# LIC_rack_CV-01.net
KiCad netlist of a schematic drawn in EAGLE
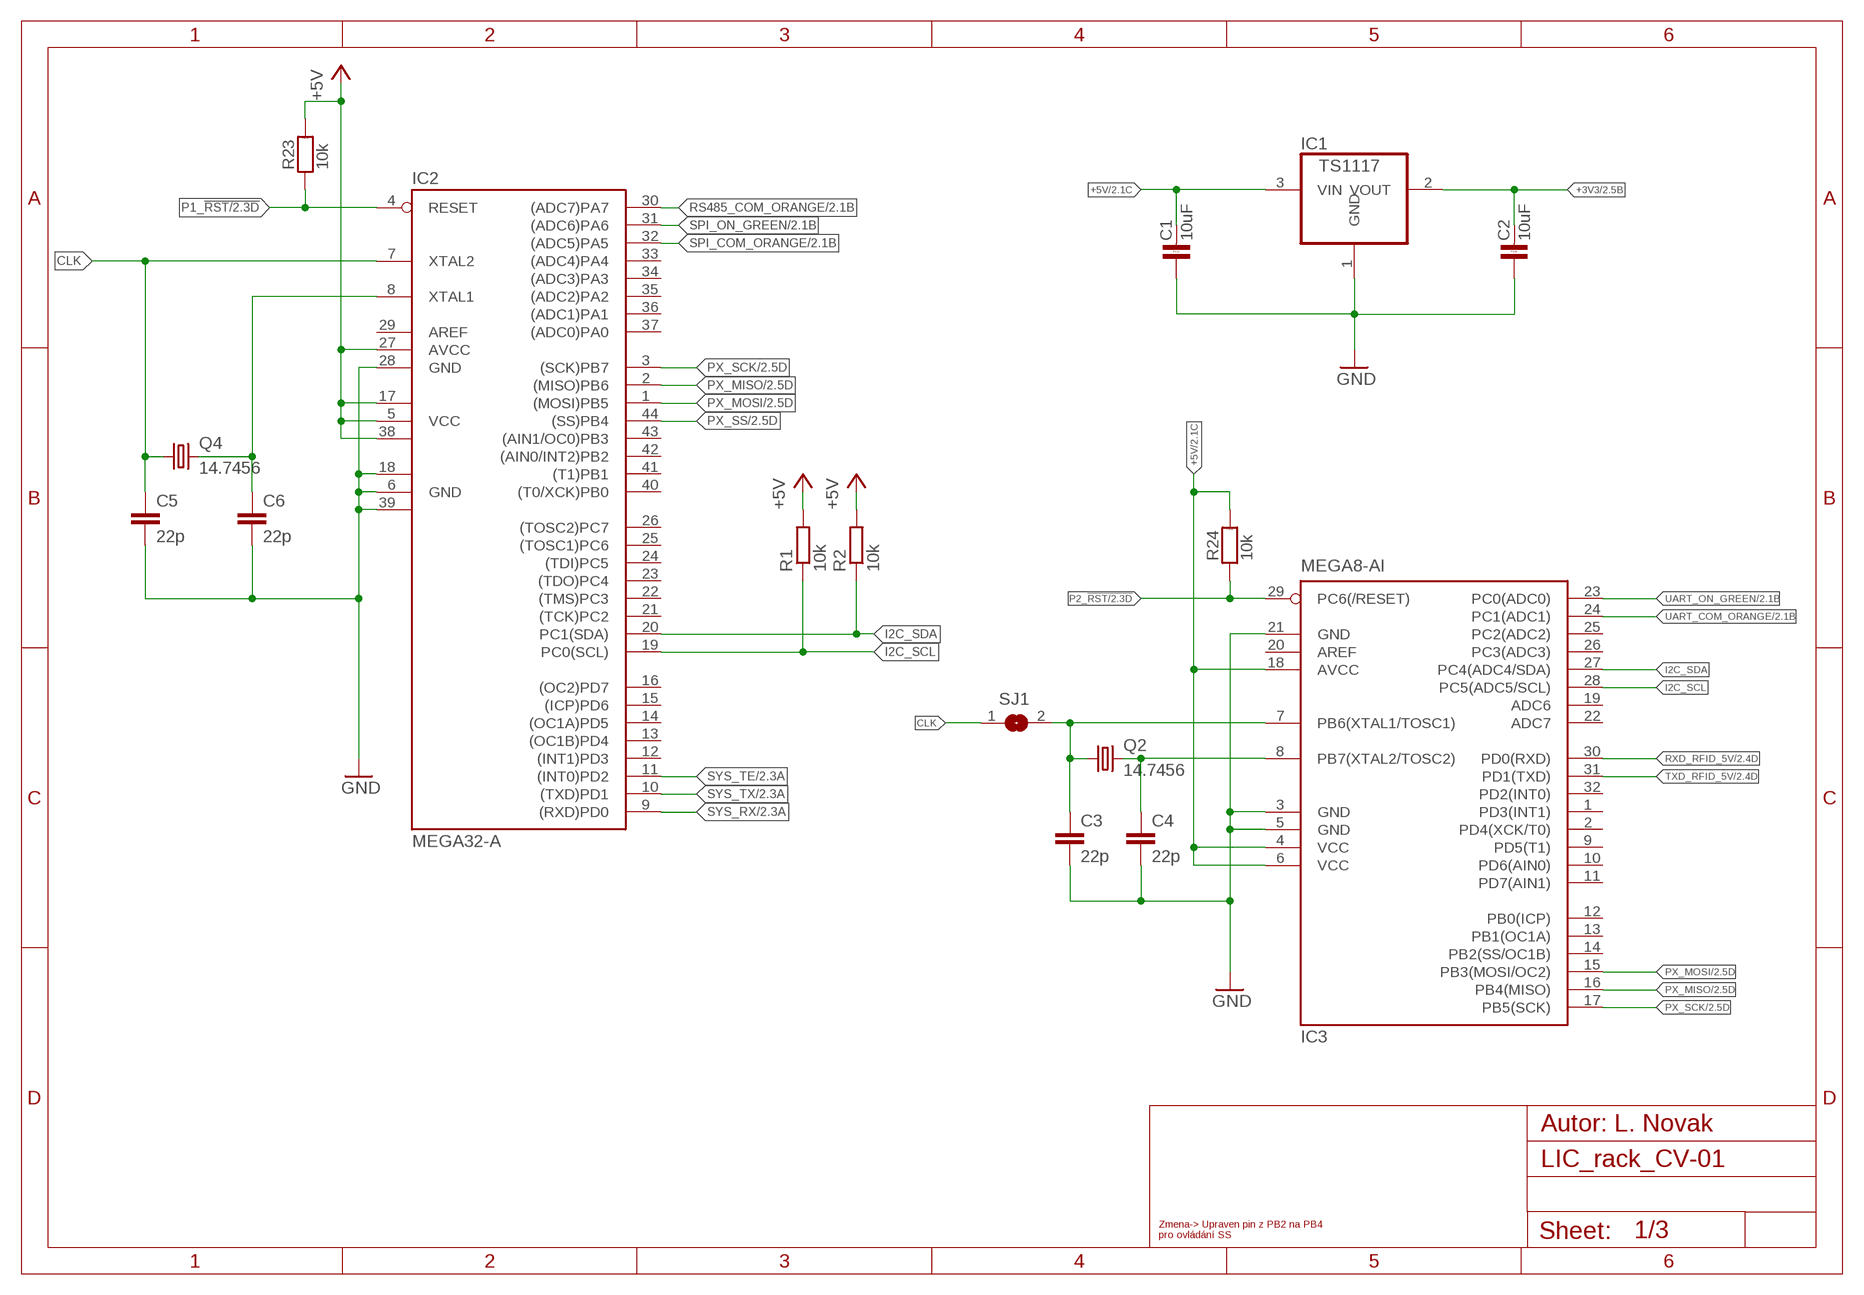
[diagram p0: schematic, sheet 1]
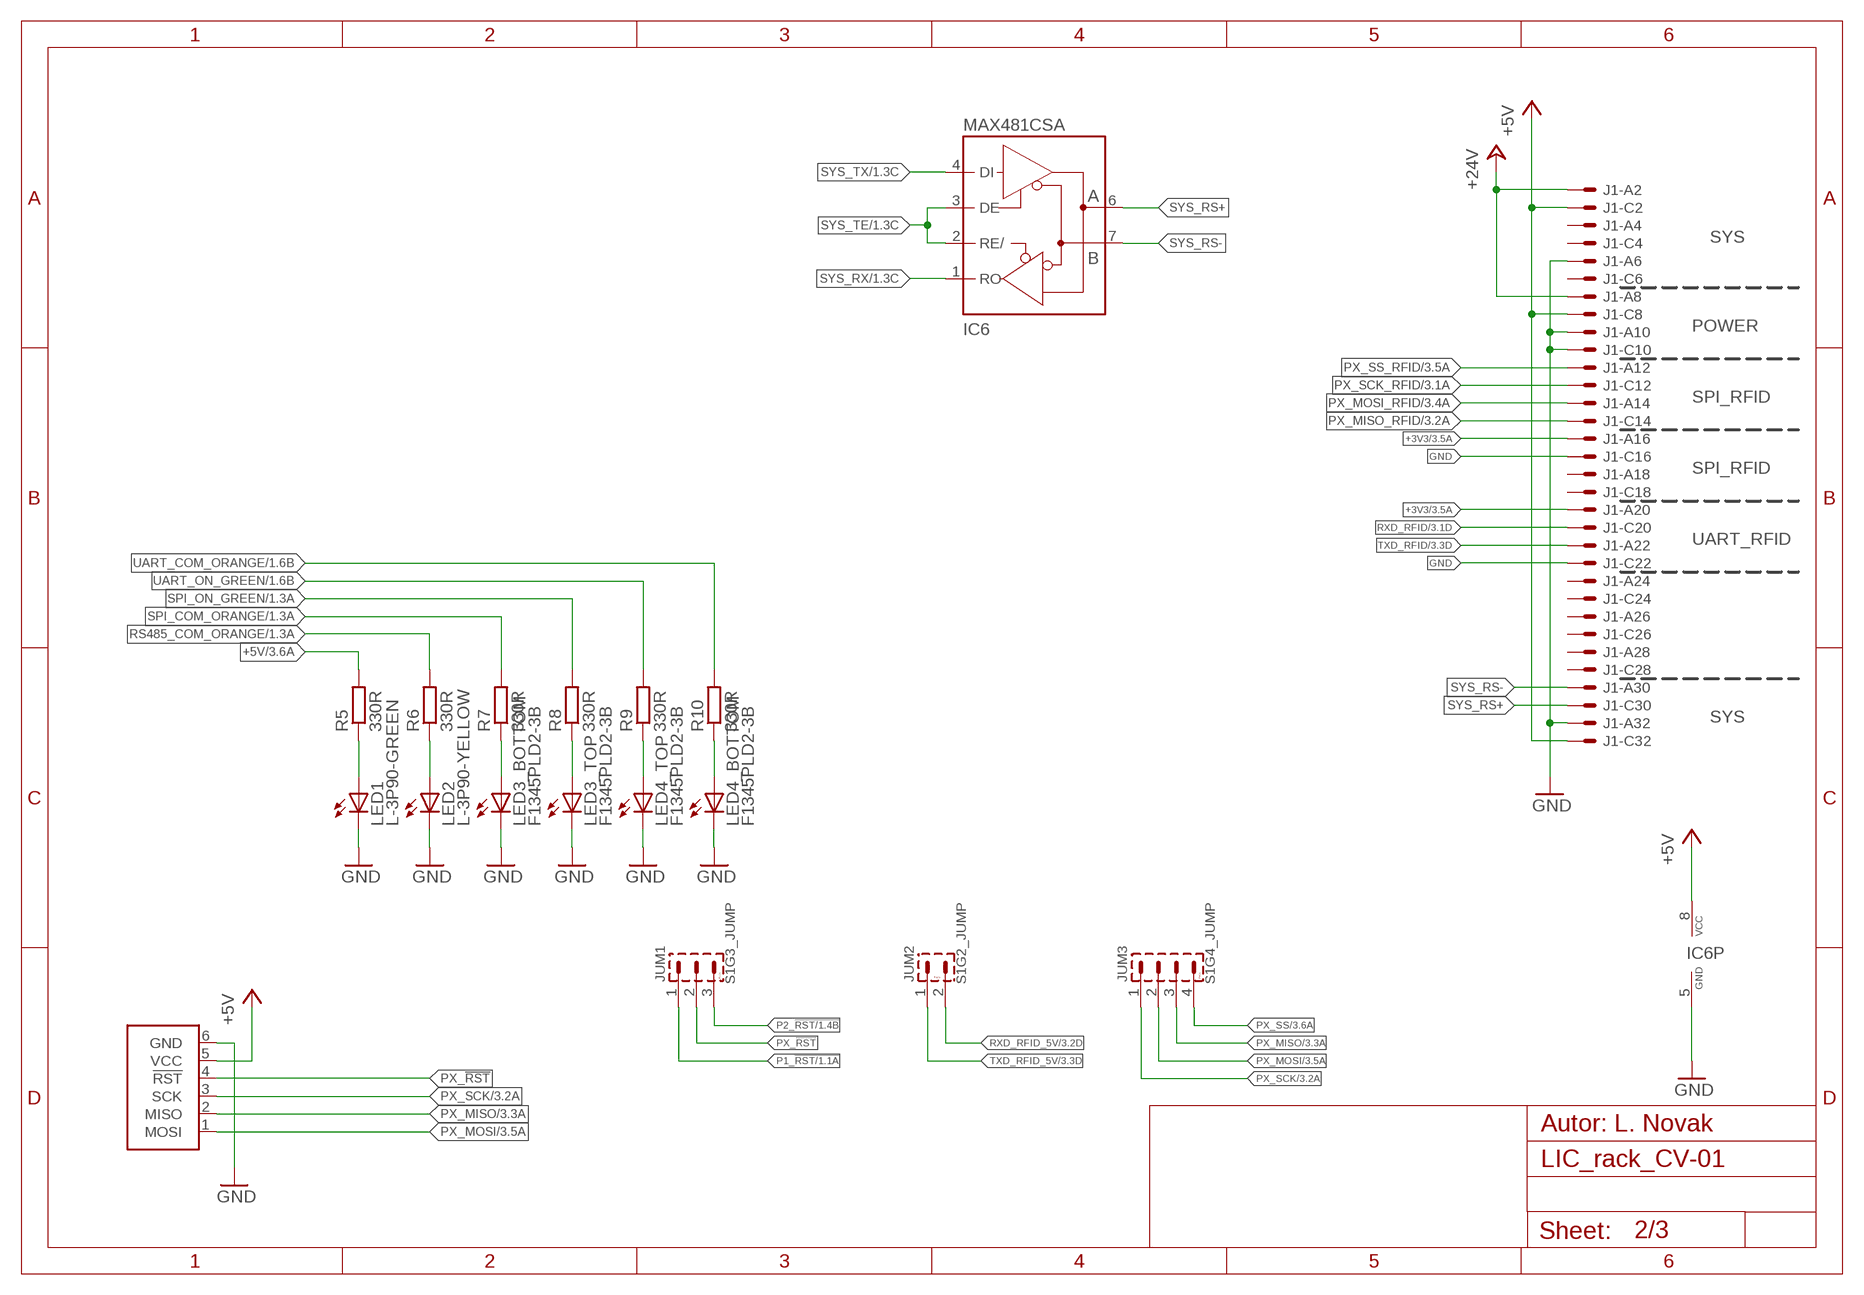
[diagram p1: schematic, sheet 2]
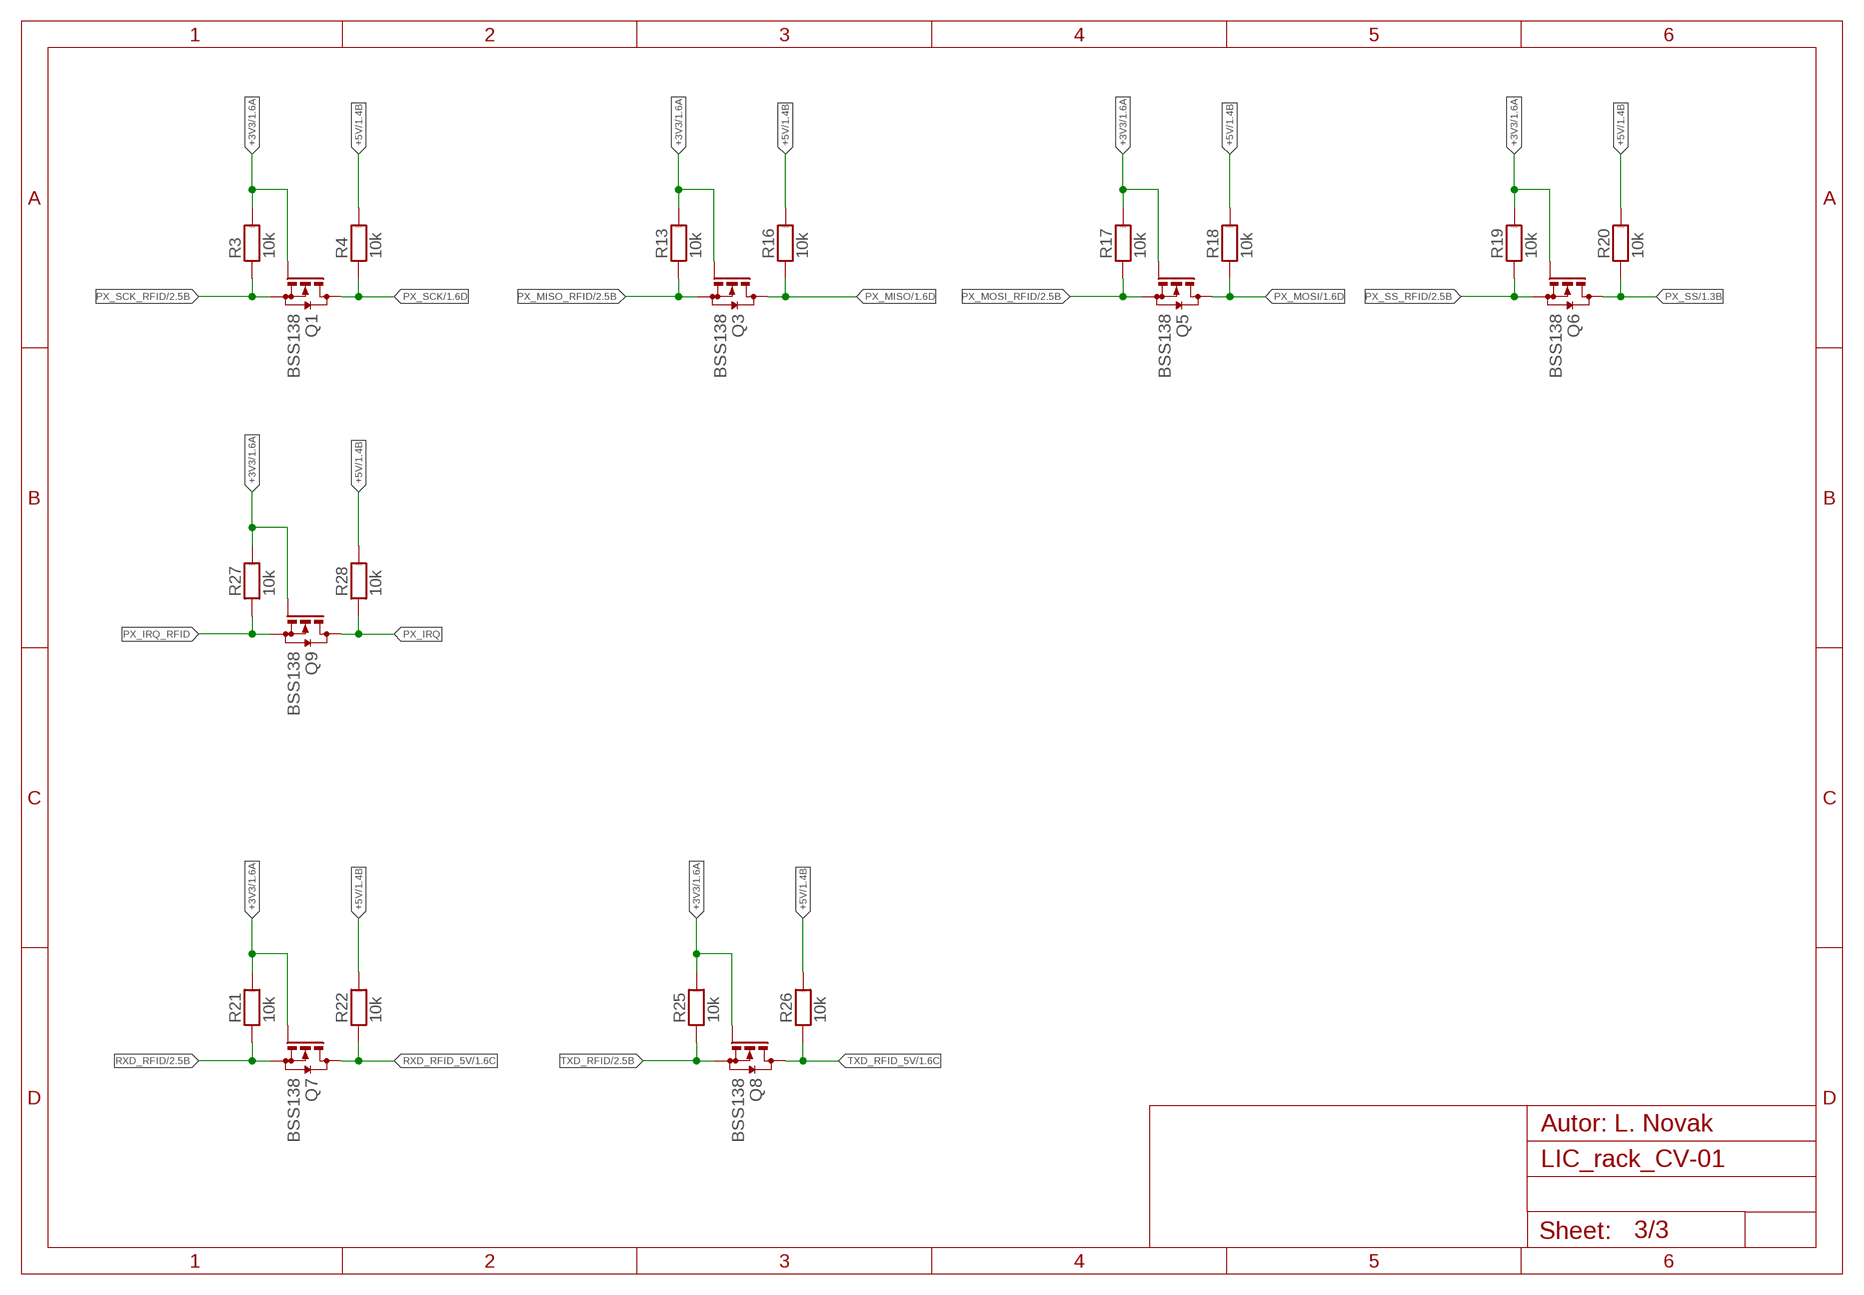
[diagram p2: schematic, sheet 3]

(export (version "E")
  (design (tool "Eeschema 10.0.6"))
  (components
    (comp (ref "C1")
      (value "10uF")
      (footprint "eagle-import:1206")
      (libsource (lib "eagle-import") (part "C-KER_1206"))
    )
    (comp (ref "C2")
      (value "10uF")
      (footprint "eagle-import:1206")
      (libsource (lib "eagle-import") (part "C-KER_1206"))
    )
    (comp (ref "C3")
      (value "22p")
      (footprint "eagle-import:C0805")
      (libsource (lib "eagle-import") (part "C-EUC0805"))
    )
    (comp (ref "C4")
      (value "22p")
      (footprint "eagle-import:C0805")
      (libsource (lib "eagle-import") (part "C-EUC0805"))
    )
    (comp (ref "C5")
      (value "22p")
      (footprint "eagle-import:C0805")
      (libsource (lib "eagle-import") (part "C-EUC0805"))
    )
    (comp (ref "C6")
      (value "22p")
      (footprint "eagle-import:C0805")
      (libsource (lib "eagle-import") (part "C-EUC0805"))
    )
    (comp (ref "IC1")
      (value "TS1117")
      (footprint "eagle-import:SOT223")
      (fields (field (name "MPN") "REG1117"))
      (libsource (lib "eagle-import") (part "REG1117"))
    )
    (comp (ref "IC2")
      (value "MEGA32-A")
      (footprint "eagle-import:TQFP44")
      (fields (field (name "MPN") "ATMEGA32-16AU"))
      (libsource (lib "eagle-import") (part "MEGA32-A"))
    )
    (comp (ref "IC3")
      (value "MEGA8-AI")
      (footprint "eagle-import:TQFP32-08")
      (fields (field (name "MPN") "ATMEGA8-16AU"))
      (libsource (lib "eagle-import") (part "MEGA8-AI"))
    )
    (comp (ref "Q2")
      (value "14.7456")
      (footprint "eagle-import:HC49U70")
      (libsource (lib "eagle-import") (part "XTAL"))
    )
    (comp (ref "Q4")
      (value "14.7456")
      (footprint "eagle-import:HC49U70")
      (libsource (lib "eagle-import") (part "XTAL"))
    )
    (comp (ref "R1")
      (value "10k")
      (footprint "eagle-import:R1206")
      (libsource (lib "eagle-import") (part "R-EU_R1206"))
    )
    (comp (ref "R2")
      (value "10k")
      (footprint "eagle-import:R1206")
      (libsource (lib "eagle-import") (part "R-EU_R1206"))
    )
    (comp (ref "R23")
      (value "10k")
      (footprint "eagle-import:1206")
      (libsource (lib "eagle-import") (part "R_1206"))
    )
    (comp (ref "R24")
      (value "10k")
      (footprint "eagle-import:1206")
      (libsource (lib "eagle-import") (part "R_1206"))
    )
    (comp (ref "SJ1") (value "SJ") (footprint "eagle-import:SJ") (libsource (lib "eagle-import") (part "SJ")))
    (comp (ref "IC6")
      (value "MAX481CSA")
      (footprint "eagle-import:SO08")
      (libsource (lib "eagle-import") (part "MAX481CSA"))
    )
    (comp (ref "J1")
      (value "VG32SP")
      (footprint "eagle-import:VG32P")
      (libsource (lib "eagle-import") (part "VG32SP"))
    )
    (comp (ref "JUM1")
      (value "S1G3_JUMP")
      (footprint "eagle-import:S1G3_JUM")
      (libsource (lib "eagle-import") (part "S1G3_JUMP"))
    )
    (comp (ref "JUM2")
      (value "S1G2_JUMP")
      (footprint "eagle-import:S1G2_JUM")
      (libsource (lib "eagle-import") (part "S1G2_JUMP"))
    )
    (comp (ref "JUM3")
      (value "S1G4_JUMP")
      (footprint "eagle-import:S1G4_JUM")
      (libsource (lib "eagle-import") (part "S1G4_JUMP"))
    )
    (comp (ref "LED1")
      (value "L-3P90-GREEN")
      (footprint "eagle-import:L-3P90")
      (libsource (lib "eagle-import") (part "L-3P90-GREEN"))
    )
    (comp (ref "LED2")
      (value "L-3P90-YELLOW")
      (footprint "eagle-import:L-3P90")
      (libsource (lib "eagle-import") (part "L-3P90-YELLOW"))
    )
    (comp (ref "LED3")
      (value "F1345PLD2-3B")
      (footprint "eagle-import:F1345PLD2-3B")
      (libsource (lib "eagle-import") (part "F1345PLD2-3B"))
    )
    (comp (ref "LED4")
      (value "F1345PLD2-3B")
      (footprint "eagle-import:F1345PLD2-3B")
      (libsource (lib "eagle-import") (part "F1345PLD2-3B"))
    )
    (comp (ref "R5")
      (value "330R")
      (footprint "eagle-import:R1206")
      (libsource (lib "eagle-import") (part "R-EU_R1206"))
    )
    (comp (ref "R6")
      (value "330R")
      (footprint "eagle-import:R1206")
      (libsource (lib "eagle-import") (part "R-EU_R1206"))
    )
    (comp (ref "R7")
      (value "330R")
      (footprint "eagle-import:R1206")
      (libsource (lib "eagle-import") (part "R-EU_R1206"))
    )
    (comp (ref "R8")
      (value "330R")
      (footprint "eagle-import:R1206")
      (libsource (lib "eagle-import") (part "R-EU_R1206"))
    )
    (comp (ref "R9")
      (value "330R")
      (footprint "eagle-import:R1206")
      (libsource (lib "eagle-import") (part "R-EU_R1206"))
    )
    (comp (ref "R10")
      (value "330R")
      (footprint "eagle-import:R1206")
      (libsource (lib "eagle-import") (part "R-EU_R1206"))
    )
    (comp (ref "U1")
      (value "ATPROG-V")
      (footprint "eagle-import:6410-06")
      (libsource (lib "eagle-import") (part "ATPROG-V"))
    )
    (comp (ref "Q1")
      (value "BSS138")
      (footprint "eagle-import:SOT23")
      (libsource (lib "eagle-import") (part "BSS123"))
    )
    (comp (ref "Q3")
      (value "BSS138")
      (footprint "eagle-import:SOT23")
      (libsource (lib "eagle-import") (part "BSS123"))
    )
    (comp (ref "Q5")
      (value "BSS138")
      (footprint "eagle-import:SOT23")
      (libsource (lib "eagle-import") (part "BSS123"))
    )
    (comp (ref "Q6")
      (value "BSS138")
      (footprint "eagle-import:SOT23")
      (libsource (lib "eagle-import") (part "BSS123"))
    )
    (comp (ref "Q7")
      (value "BSS138")
      (footprint "eagle-import:SOT23")
      (libsource (lib "eagle-import") (part "BSS123"))
    )
    (comp (ref "Q8")
      (value "BSS138")
      (footprint "eagle-import:SOT23")
      (libsource (lib "eagle-import") (part "BSS123"))
    )
    (comp (ref "Q9")
      (value "BSS138")
      (footprint "eagle-import:SOT23")
      (libsource (lib "eagle-import") (part "BSS123"))
    )
    (comp (ref "R3")
      (value "10k")
      (footprint "eagle-import:1206")
      (libsource (lib "eagle-import") (part "R_1206"))
    )
    (comp (ref "R4")
      (value "10k")
      (footprint "eagle-import:1206")
      (libsource (lib "eagle-import") (part "R_1206"))
    )
    (comp (ref "R13")
      (value "10k")
      (footprint "eagle-import:1206")
      (libsource (lib "eagle-import") (part "R_1206"))
    )
    (comp (ref "R16")
      (value "10k")
      (footprint "eagle-import:1206")
      (libsource (lib "eagle-import") (part "R_1206"))
    )
    (comp (ref "R17")
      (value "10k")
      (footprint "eagle-import:1206")
      (libsource (lib "eagle-import") (part "R_1206"))
    )
    (comp (ref "R18")
      (value "10k")
      (footprint "eagle-import:1206")
      (libsource (lib "eagle-import") (part "R_1206"))
    )
    (comp (ref "R19")
      (value "10k")
      (footprint "eagle-import:1206")
      (libsource (lib "eagle-import") (part "R_1206"))
    )
    (comp (ref "R20")
      (value "10k")
      (footprint "eagle-import:1206")
      (libsource (lib "eagle-import") (part "R_1206"))
    )
    (comp (ref "R21")
      (value "10k")
      (footprint "eagle-import:1206")
      (libsource (lib "eagle-import") (part "R_1206"))
    )
    (comp (ref "R22")
      (value "10k")
      (footprint "eagle-import:1206")
      (libsource (lib "eagle-import") (part "R_1206"))
    )
    (comp (ref "R25")
      (value "10k")
      (footprint "eagle-import:1206")
      (libsource (lib "eagle-import") (part "R_1206"))
    )
    (comp (ref "R26")
      (value "10k")
      (footprint "eagle-import:1206")
      (libsource (lib "eagle-import") (part "R_1206"))
    )
    (comp (ref "R27")
      (value "10k")
      (footprint "eagle-import:1206")
      (libsource (lib "eagle-import") (part "R_1206"))
    )
    (comp (ref "R28")
      (value "10k")
      (footprint "eagle-import:1206")
      (libsource (lib "eagle-import") (part "R_1206"))
    )
  )
  (nets
    (net (code "1") (name "+3V3") (class "Default")
      (node (ref "C2") (pin "2") (pinfunction "2_2") (pintype "passive"))
      (node (ref "IC1") (pin "2") (pinfunction "VOUT_2") (pintype "output"))
      (node (ref "J1") (pin "A16") (pinfunction "MS_A16") (pintype "passive"))
      (node (ref "J1") (pin "A20") (pinfunction "MS_A20") (pintype "passive"))
      (node (ref "Q1") (pin "1") (pinfunction "G_1") (pintype "passive"))
      (node (ref "Q3") (pin "1") (pinfunction "G_1") (pintype "passive"))
      (node (ref "Q5") (pin "1") (pinfunction "G_1") (pintype "passive"))
      (node (ref "Q6") (pin "1") (pinfunction "G_1") (pintype "passive"))
      (node (ref "Q7") (pin "1") (pinfunction "G_1") (pintype "passive"))
      (node (ref "Q8") (pin "1") (pinfunction "G_1") (pintype "passive"))
      (node (ref "Q9") (pin "1") (pinfunction "G_1") (pintype "passive"))
      (node (ref "R13") (pin "2") (pinfunction "2_2") (pintype "passive"))
      (node (ref "R17") (pin "2") (pinfunction "2_2") (pintype "passive"))
      (node (ref "R19") (pin "2") (pinfunction "2_2") (pintype "passive"))
      (node (ref "R21") (pin "2") (pinfunction "2_2") (pintype "passive"))
      (node (ref "R25") (pin "2") (pinfunction "2_2") (pintype "passive"))
      (node (ref "R27") (pin "2") (pinfunction "2_2") (pintype "passive"))
      (node (ref "R3") (pin "2") (pinfunction "2_2") (pintype "passive"))
    )
    (net (code "2") (name "+5V") (class "Default")
      (node (ref "C1") (pin "2") (pinfunction "2_2") (pintype "passive"))
      (node (ref "IC1") (pin "3") (pinfunction "VIN_3") (pintype "input"))
      (node (ref "IC2") (pin "17") (pinfunction "VCC1_17") (pintype "power_in"))
      (node (ref "IC2") (pin "27") (pinfunction "AVCC_27") (pintype "power_in"))
      (node (ref "IC2") (pin "38") (pinfunction "VCC2_38") (pintype "power_in"))
      (node (ref "IC2") (pin "5") (pinfunction "VCC_5") (pintype "power_in"))
      (node (ref "IC3") (pin "18") (pinfunction "AVCC_18") (pintype "power_in"))
      (node (ref "IC3") (pin "4") (pinfunction "VCC_4") (pintype "power_in"))
      (node (ref "IC3") (pin "6") (pinfunction "VCC_6") (pintype "power_in"))
      (node (ref "IC6") (pin "8") (pinfunction "VCC_8") (pintype "power_in"))
      (node (ref "J1") (pin "C2") (pinfunction "MS_C2") (pintype "passive"))
      (node (ref "J1") (pin "C32") (pinfunction "MSV_C32") (pintype "passive"))
      (node (ref "J1") (pin "C8") (pinfunction "MS_C8") (pintype "passive"))
      (node (ref "R1") (pin "2") (pinfunction "2_2") (pintype "passive"))
      (node (ref "R16") (pin "2") (pinfunction "2_2") (pintype "passive"))
      (node (ref "R18") (pin "2") (pinfunction "2_2") (pintype "passive"))
      (node (ref "R2") (pin "2") (pinfunction "2_2") (pintype "passive"))
      (node (ref "R20") (pin "2") (pinfunction "2_2") (pintype "passive"))
      (node (ref "R22") (pin "2") (pinfunction "2_2") (pintype "passive"))
      (node (ref "R23") (pin "2") (pinfunction "2_2") (pintype "passive"))
      (node (ref "R24") (pin "2") (pinfunction "2_2") (pintype "passive"))
      (node (ref "R26") (pin "2") (pinfunction "2_2") (pintype "passive"))
      (node (ref "R28") (pin "2") (pinfunction "2_2") (pintype "passive"))
      (node (ref "R4") (pin "2") (pinfunction "2_2") (pintype "passive"))
      (node (ref "R5") (pin "2") (pinfunction "2_2") (pintype "passive"))
      (node (ref "U1") (pin "5") (pinfunction "VCC_5") (pintype "power_in"))
    )
    (net (code "3") (name "+24V") (class "Default")
      (node (ref "J1") (pin "A2") (pinfunction "MS_A2") (pintype "passive"))
      (node (ref "J1") (pin "A8") (pinfunction "MS_A8") (pintype "passive"))
    )
    (net (code "4") (name "CLK") (class "Default")
      (node (ref "C5") (pin "1") (pinfunction "1_1") (pintype "passive"))
      (node (ref "IC2") (pin "7") (pinfunction "XTAL2_7") (pintype "bidirectional"))
      (node (ref "Q4") (pin "1") (pinfunction "1_1") (pintype "passive"))
      (node (ref "SJ1") (pin "1") (pinfunction "1_1") (pintype "passive"))
    )
    (net (code "5") (name "GND") (class "Default")
      (node (ref "C1") (pin "1") (pinfunction "1_1") (pintype "passive"))
      (node (ref "C2") (pin "1") (pinfunction "1_1") (pintype "passive"))
      (node (ref "C3") (pin "2") (pinfunction "2_2") (pintype "passive"))
      (node (ref "C4") (pin "2") (pinfunction "2_2") (pintype "passive"))
      (node (ref "C5") (pin "2") (pinfunction "2_2") (pintype "passive"))
      (node (ref "C6") (pin "2") (pinfunction "2_2") (pintype "passive"))
      (node (ref "IC1") (pin "1") (pinfunction "GND_1") (pintype "power_in"))
      (node (ref "IC2") (pin "18") (pinfunction "GND1_18") (pintype "power_in"))
      (node (ref "IC2") (pin "28") (pinfunction "GND_28") (pintype "power_in"))
      (node (ref "IC2") (pin "39") (pinfunction "GND2_39") (pintype "power_in"))
      (node (ref "IC2") (pin "6") (pinfunction "GND_6") (pintype "power_in"))
      (node (ref "IC3") (pin "21") (pinfunction "GND_21") (pintype "power_in"))
      (node (ref "IC3") (pin "3") (pinfunction "GND_3") (pintype "power_in"))
      (node (ref "IC3") (pin "5") (pinfunction "GND_5") (pintype "power_in"))
      (node (ref "IC6") (pin "5") (pinfunction "GND_5") (pintype "power_in"))
      (node (ref "J1") (pin "A10") (pinfunction "MS_A10") (pintype "passive"))
      (node (ref "J1") (pin "A32") (pinfunction "MS_A32") (pintype "passive"))
      (node (ref "J1") (pin "A6") (pinfunction "MS_A6") (pintype "passive"))
      (node (ref "J1") (pin "C10") (pinfunction "MS_C10") (pintype "passive"))
      (node (ref "J1") (pin "C16") (pinfunction "MS_C16") (pintype "passive"))
      (node (ref "J1") (pin "C22") (pinfunction "MS_C22") (pintype "passive"))
      (node (ref "LED1") (pin "K") (pinfunction "C_K") (pintype "passive"))
      (node (ref "LED2") (pin "K") (pinfunction "C_K") (pintype "passive"))
      (node (ref "LED3") (pin "1K") (pinfunction "C_1K") (pintype "passive"))
      (node (ref "LED3") (pin "2K") (pinfunction "C_2K") (pintype "passive"))
      (node (ref "LED4") (pin "1K") (pinfunction "C_1K") (pintype "passive"))
      (node (ref "LED4") (pin "2K") (pinfunction "C_2K") (pintype "passive"))
      (node (ref "U1") (pin "6") (pinfunction "GND_6") (pintype "power_in"))
    )
    (net (code "6") (name "I2C_SCL") (class "Default")
      (node (ref "IC2") (pin "19") (pinfunction "PC0(SCL)_19") (pintype "bidirectional"))
      (node (ref "IC3") (pin "28") (pinfunction "PC5(ADC5/SCL)_28") (pintype "bidirectional"))
      (node (ref "R1") (pin "1") (pinfunction "1_1") (pintype "passive"))
    )
    (net (code "7") (name "I2C_SDA") (class "Default")
      (node (ref "IC2") (pin "20") (pinfunction "PC1(SDA)_20") (pintype "bidirectional"))
      (node (ref "IC3") (pin "27") (pinfunction "PC4(ADC4/SDA)_27") (pintype "bidirectional"))
      (node (ref "R2") (pin "1") (pinfunction "1_1") (pintype "passive"))
    )
    (net (code "8") (name "Net-(IC2-XTAL1)") (class "Default")
      (node (ref "C6") (pin "1") (pinfunction "1_1") (pintype "passive"))
      (node (ref "IC2") (pin "8") (pinfunction "XTAL1_8") (pintype "bidirectional"))
      (node (ref "Q4") (pin "2") (pinfunction "2_2") (pintype "passive"))
    )
    (net (code "9") (name "Net-(IC3-PB6(XTAL1{slash}TOSC1))") (class "Default")
      (node (ref "C3") (pin "1") (pinfunction "1_1") (pintype "passive"))
      (node (ref "IC3") (pin "7") (pinfunction "PB6(XTAL1/TOSC1)_7") (pintype "bidirectional"))
      (node (ref "Q2") (pin "1") (pinfunction "1_1") (pintype "passive"))
      (node (ref "SJ1") (pin "2") (pinfunction "2_2") (pintype "passive"))
    )
    (net (code "10") (name "Net-(IC3-PB7(XTAL2{slash}TOSC2))") (class "Default")
      (node (ref "C4") (pin "1") (pinfunction "1_1") (pintype "passive"))
      (node (ref "IC3") (pin "8") (pinfunction "PB7(XTAL2/TOSC2)_8") (pintype "bidirectional"))
      (node (ref "Q2") (pin "2") (pinfunction "2_2") (pintype "passive"))
    )
    (net (code "11") (name "Net-(LED1-PadA)") (class "Default")
      (node (ref "LED1") (pin "A") (pinfunction "A_A") (pintype "passive"))
      (node (ref "R5") (pin "1") (pinfunction "1_1") (pintype "passive"))
    )
    (net (code "12") (name "Net-(LED2-PadA)") (class "Default")
      (node (ref "LED2") (pin "A") (pinfunction "A_A") (pintype "passive"))
      (node (ref "R6") (pin "1") (pinfunction "1_1") (pintype "passive"))
    )
    (net (code "13") (name "Net-(LED3A-A)") (class "Default")
      (node (ref "LED3") (pin "1A") (pinfunction "A_1A") (pintype "passive"))
      (node (ref "R7") (pin "1") (pinfunction "1_1") (pintype "passive"))
    )
    (net (code "14") (name "Net-(LED3B-A)") (class "Default")
      (node (ref "LED3") (pin "2A") (pinfunction "A_2A") (pintype "passive"))
      (node (ref "R8") (pin "1") (pinfunction "1_1") (pintype "passive"))
    )
    (net (code "15") (name "Net-(LED4A-A)") (class "Default")
      (node (ref "LED4") (pin "1A") (pinfunction "A_1A") (pintype "passive"))
      (node (ref "R10") (pin "1") (pinfunction "1_1") (pintype "passive"))
    )
    (net (code "16") (name "Net-(LED4B-A)") (class "Default")
      (node (ref "LED4") (pin "2A") (pinfunction "A_2A") (pintype "passive"))
      (node (ref "R9") (pin "1") (pinfunction "1_1") (pintype "passive"))
    )
    (net (code "17") (name "P1_~{RST}") (class "Default")
      (node (ref "IC2") (pin "4") (pinfunction "RESET_4") (pintype "input"))
      (node (ref "JUM1") (pin "1") (pinfunction "1_1") (pintype "passive"))
      (node (ref "R23") (pin "1") (pinfunction "1_1") (pintype "passive"))
    )
    (net (code "18") (name "P2_~{RST}") (class "Default")
      (node (ref "IC3") (pin "29") (pinfunction "PC6(/RESET)_29") (pintype "bidirectional"))
      (node (ref "JUM1") (pin "3") (pinfunction "3_3") (pintype "passive"))
      (node (ref "R24") (pin "1") (pinfunction "1_1") (pintype "passive"))
    )
    (net (code "19") (name "PX_IRQ") (class "Default")
      (node (ref "Q9") (pin "3") (pinfunction "D_3") (pintype "passive"))
      (node (ref "R28") (pin "1") (pinfunction "1_1") (pintype "passive"))
    )
    (net (code "20") (name "PX_IRQ_RFID") (class "Default")
      (node (ref "Q9") (pin "2") (pinfunction "S_2") (pintype "passive"))
      (node (ref "R27") (pin "1") (pinfunction "1_1") (pintype "passive"))
    )
    (net (code "21") (name "PX_MISO") (class "Default")
      (node (ref "IC2") (pin "2") (pinfunction "(MISO)PB6_2") (pintype "bidirectional"))
      (node (ref "IC3") (pin "16") (pinfunction "PB4(MISO)_16") (pintype "bidirectional"))
      (node (ref "JUM3") (pin "3") (pinfunction "3_3") (pintype "passive"))
      (node (ref "Q3") (pin "3") (pinfunction "D_3") (pintype "passive"))
      (node (ref "R16") (pin "1") (pinfunction "1_1") (pintype "passive"))
      (node (ref "U1") (pin "2") (pinfunction "MISO_2") (pintype "input"))
    )
    (net (code "22") (name "PX_MISO_RFID") (class "Default")
      (node (ref "J1") (pin "C14") (pinfunction "MS_C14") (pintype "passive"))
      (node (ref "Q3") (pin "2") (pinfunction "S_2") (pintype "passive"))
      (node (ref "R13") (pin "1") (pinfunction "1_1") (pintype "passive"))
    )
    (net (code "23") (name "PX_MOSI") (class "Default")
      (node (ref "IC2") (pin "1") (pinfunction "(MOSI)PB5_1") (pintype "bidirectional"))
      (node (ref "IC3") (pin "15") (pinfunction "PB3(MOSI/OC2)_15") (pintype "bidirectional"))
      (node (ref "JUM3") (pin "2") (pinfunction "2_2") (pintype "passive"))
      (node (ref "Q5") (pin "3") (pinfunction "D_3") (pintype "passive"))
      (node (ref "R18") (pin "1") (pinfunction "1_1") (pintype "passive"))
      (node (ref "U1") (pin "1") (pinfunction "MOSI_1") (pintype "output"))
    )
    (net (code "24") (name "PX_MOSI_RFID") (class "Default")
      (node (ref "J1") (pin "A14") (pinfunction "MS_A14") (pintype "passive"))
      (node (ref "Q5") (pin "2") (pinfunction "S_2") (pintype "passive"))
      (node (ref "R17") (pin "1") (pinfunction "1_1") (pintype "passive"))
    )
    (net (code "25") (name "PX_SCK") (class "Default")
      (node (ref "IC2") (pin "3") (pinfunction "(SCK)PB7_3") (pintype "bidirectional"))
      (node (ref "IC3") (pin "17") (pinfunction "PB5(SCK)_17") (pintype "bidirectional"))
      (node (ref "JUM3") (pin "1") (pinfunction "1_1") (pintype "passive"))
      (node (ref "Q1") (pin "3") (pinfunction "D_3") (pintype "passive"))
      (node (ref "R4") (pin "1") (pinfunction "1_1") (pintype "passive"))
      (node (ref "U1") (pin "3") (pinfunction "SCK_3") (pintype "input"))
    )
    (net (code "26") (name "PX_SCK_RFID") (class "Default")
      (node (ref "J1") (pin "C12") (pinfunction "MS_C12") (pintype "passive"))
      (node (ref "Q1") (pin "2") (pinfunction "S_2") (pintype "passive"))
      (node (ref "R3") (pin "1") (pinfunction "1_1") (pintype "passive"))
    )
    (net (code "27") (name "PX_SS") (class "Default")
      (node (ref "IC2") (pin "44") (pinfunction "(SS)PB4_44") (pintype "bidirectional"))
      (node (ref "JUM3") (pin "4") (pinfunction "4_4") (pintype "passive"))
      (node (ref "Q6") (pin "3") (pinfunction "D_3") (pintype "passive"))
      (node (ref "R20") (pin "1") (pinfunction "1_1") (pintype "passive"))
    )
    (net (code "28") (name "PX_SS_RFID") (class "Default")
      (node (ref "J1") (pin "A12") (pinfunction "MS_A12") (pintype "passive"))
      (node (ref "Q6") (pin "2") (pinfunction "S_2") (pintype "passive"))
      (node (ref "R19") (pin "1") (pinfunction "1_1") (pintype "passive"))
    )
    (net (code "29") (name "PX_~{RST}") (class "Default")
      (node (ref "JUM1") (pin "2") (pinfunction "2_2") (pintype "passive"))
      (node (ref "U1") (pin "4") (pinfunction "~{RST}_4") (pintype "input"))
    )
    (net (code "30") (name "RS485_COM_ORANGE") (class "Default")
      (node (ref "IC2") (pin "30") (pinfunction "(ADC7)PA7_30") (pintype "bidirectional"))
      (node (ref "R6") (pin "2") (pinfunction "2_2") (pintype "passive"))
    )
    (net (code "31") (name "RXD_RFID") (class "Default")
      (node (ref "J1") (pin "C20") (pinfunction "MS_C20") (pintype "passive"))
      (node (ref "Q7") (pin "2") (pinfunction "S_2") (pintype "passive"))
      (node (ref "R21") (pin "1") (pinfunction "1_1") (pintype "passive"))
    )
    (net (code "32") (name "RXD_RFID_5V") (class "Default")
      (node (ref "IC3") (pin "30") (pinfunction "PD0(RXD)_30") (pintype "bidirectional"))
      (node (ref "JUM2") (pin "2") (pinfunction "2_2") (pintype "passive"))
      (node (ref "Q7") (pin "3") (pinfunction "D_3") (pintype "passive"))
      (node (ref "R22") (pin "1") (pinfunction "1_1") (pintype "passive"))
    )
    (net (code "33") (name "SPI_COM_ORANGE") (class "Default")
      (node (ref "IC2") (pin "32") (pinfunction "(ADC5)PA5_32") (pintype "bidirectional"))
      (node (ref "R7") (pin "2") (pinfunction "2_2") (pintype "passive"))
    )
    (net (code "34") (name "SPI_ON_GREEN") (class "Default")
      (node (ref "IC2") (pin "31") (pinfunction "(ADC6)PA6_31") (pintype "bidirectional"))
      (node (ref "R8") (pin "2") (pinfunction "2_2") (pintype "passive"))
    )
    (net (code "35") (name "SYS_RS+") (class "Default")
      (node (ref "IC6") (pin "6") (pinfunction "A_6") (pintype "passive"))
      (node (ref "J1") (pin "C30") (pinfunction "MS_C30") (pintype "passive"))
    )
    (net (code "36") (name "SYS_RS-") (class "Default")
      (node (ref "IC6") (pin "7") (pinfunction "B_7") (pintype "passive"))
      (node (ref "J1") (pin "A30") (pinfunction "MS_A30") (pintype "passive"))
    )
    (net (code "37") (name "SYS_RX") (class "Default")
      (node (ref "IC2") (pin "9") (pinfunction "(RXD)PD0_9") (pintype "bidirectional"))
      (node (ref "IC6") (pin "1") (pinfunction "RO_1") (pintype "output"))
    )
    (net (code "38") (name "SYS_TE") (class "Default")
      (node (ref "IC2") (pin "11") (pinfunction "(INT0)PD2_11") (pintype "bidirectional"))
      (node (ref "IC6") (pin "2") (pinfunction "RE/_2") (pintype "input"))
      (node (ref "IC6") (pin "3") (pinfunction "DE_3") (pintype "input"))
    )
    (net (code "39") (name "SYS_TX") (class "Default")
      (node (ref "IC2") (pin "10") (pinfunction "(TXD)PD1_10") (pintype "bidirectional"))
      (node (ref "IC6") (pin "4") (pinfunction "DI_4") (pintype "input"))
    )
    (net (code "40") (name "TXD_RFID") (class "Default")
      (node (ref "J1") (pin "A22") (pinfunction "MS_A22") (pintype "passive"))
      (node (ref "Q8") (pin "2") (pinfunction "S_2") (pintype "passive"))
      (node (ref "R25") (pin "1") (pinfunction "1_1") (pintype "passive"))
    )
    (net (code "41") (name "TXD_RFID_5V") (class "Default")
      (node (ref "IC3") (pin "31") (pinfunction "PD1(TXD)_31") (pintype "bidirectional"))
      (node (ref "JUM2") (pin "1") (pinfunction "1_1") (pintype "passive"))
      (node (ref "Q8") (pin "3") (pinfunction "D_3") (pintype "passive"))
      (node (ref "R26") (pin "1") (pinfunction "1_1") (pintype "passive"))
    )
    (net (code "42") (name "UART_COM_ORANGE") (class "Default")
      (node (ref "IC3") (pin "24") (pinfunction "PC1(ADC1)_24") (pintype "bidirectional"))
      (node (ref "R10") (pin "2") (pinfunction "2_2") (pintype "passive"))
    )
    (net (code "43") (name "UART_ON_GREEN") (class "Default")
      (node (ref "IC3") (pin "23") (pinfunction "PC0(ADC0)_23") (pintype "bidirectional"))
      (node (ref "R9") (pin "2") (pinfunction "2_2") (pintype "passive"))
    )
    (net (code "44") (name "unconnected-(IC2-(ADC0)PA0-Pad37)") (class "Default")
      (node (ref "IC2") (pin "37") (pinfunction "(ADC0)PA0_37") (pintype "bidirectional"))
    )
    (net (code "45") (name "unconnected-(IC2-(ADC1)PA1-Pad36)") (class "Default")
      (node (ref "IC2") (pin "36") (pinfunction "(ADC1)PA1_36") (pintype "bidirectional"))
    )
    (net (code "46") (name "unconnected-(IC2-(ADC2)PA2-Pad35)") (class "Default")
      (node (ref "IC2") (pin "35") (pinfunction "(ADC2)PA2_35") (pintype "bidirectional"))
    )
    (net (code "47") (name "unconnected-(IC2-(ADC3)PA3-Pad34)") (class "Default")
      (node (ref "IC2") (pin "34") (pinfunction "(ADC3)PA3_34") (pintype "bidirectional"))
    )
    (net (code "48") (name "unconnected-(IC2-(ADC4)PA4-Pad33)") (class "Default")
      (node (ref "IC2") (pin "33") (pinfunction "(ADC4)PA4_33") (pintype "bidirectional"))
    )
    (net (code "49") (name "unconnected-(IC2-(AIN0{slash}INT2)PB2-Pad42)") (class "Default")
      (node (ref "IC2") (pin "42") (pinfunction "(AIN0/INT2)PB2_42") (pintype "bidirectional"))
    )
    (net (code "50") (name "unconnected-(IC2-(AIN1{slash}OC0)PB3-Pad43)") (class "Default")
      (node (ref "IC2") (pin "43") (pinfunction "(AIN1/OC0)PB3_43") (pintype "bidirectional"))
    )
    (net (code "51") (name "unconnected-(IC2-(ICP)PD6-Pad15)") (class "Default")
      (node (ref "IC2") (pin "15") (pinfunction "(ICP)PD6_15") (pintype "bidirectional"))
    )
    (net (code "52") (name "unconnected-(IC2-(INT1)PD3-Pad12)") (class "Default")
      (node (ref "IC2") (pin "12") (pinfunction "(INT1)PD3_12") (pintype "bidirectional"))
    )
    (net (code "53") (name "unconnected-(IC2-(OC1A)PD5-Pad14)") (class "Default")
      (node (ref "IC2") (pin "14") (pinfunction "(OC1A)PD5_14") (pintype "bidirectional"))
    )
    (net (code "54") (name "unconnected-(IC2-(OC1B)PD4-Pad13)") (class "Default")
      (node (ref "IC2") (pin "13") (pinfunction "(OC1B)PD4_13") (pintype "bidirectional"))
    )
    (net (code "55") (name "unconnected-(IC2-(OC2)PD7-Pad16)") (class "Default")
      (node (ref "IC2") (pin "16") (pinfunction "(OC2)PD7_16") (pintype "bidirectional"))
    )
    (net (code "56") (name "unconnected-(IC2-(T0{slash}XCK)PB0-Pad40)") (class "Default")
      (node (ref "IC2") (pin "40") (pinfunction "(T0/XCK)PB0_40") (pintype "bidirectional"))
    )
    (net (code "57") (name "unconnected-(IC2-(T1)PB1-Pad41)") (class "Default")
      (node (ref "IC2") (pin "41") (pinfunction "(T1)PB1_41") (pintype "bidirectional"))
    )
    (net (code "58") (name "unconnected-(IC2-(TCK)PC2-Pad21)") (class "Default")
      (node (ref "IC2") (pin "21") (pinfunction "(TCK)PC2_21") (pintype "bidirectional"))
    )
    (net (code "59") (name "unconnected-(IC2-(TDI)PC5-Pad24)") (class "Default")
      (node (ref "IC2") (pin "24") (pinfunction "(TDI)PC5_24") (pintype "bidirectional"))
    )
    (net (code "60") (name "unconnected-(IC2-(TDO)PC4-Pad23)") (class "Default")
      (node (ref "IC2") (pin "23") (pinfunction "(TDO)PC4_23") (pintype "bidirectional"))
    )
    (net (code "61") (name "unconnected-(IC2-(TMS)PC3-Pad22)") (class "Default")
      (node (ref "IC2") (pin "22") (pinfunction "(TMS)PC3_22") (pintype "bidirectional"))
    )
    (net (code "62") (name "unconnected-(IC2-(TOSC1)PC6-Pad25)") (class "Default")
      (node (ref "IC2") (pin "25") (pinfunction "(TOSC1)PC6_25") (pintype "bidirectional"))
    )
    (net (code "63") (name "unconnected-(IC2-(TOSC2)PC7-Pad26)") (class "Default")
      (node (ref "IC2") (pin "26") (pinfunction "(TOSC2)PC7_26") (pintype "bidirectional"))
    )
    (net (code "64") (name "unconnected-(IC2-AREF-Pad29)") (class "Default")
      (node (ref "IC2") (pin "29") (pinfunction "AREF_29") (pintype "passive"))
    )
    (net (code "65") (name "unconnected-(IC3-ADC6-Pad19)") (class "Default")
      (node (ref "IC3") (pin "19") (pinfunction "ADC6_19") (pintype "bidirectional"))
    )
    (net (code "66") (name "unconnected-(IC3-ADC7-Pad22)") (class "Default")
      (node (ref "IC3") (pin "22") (pinfunction "ADC7_22") (pintype "bidirectional"))
    )
    (net (code "67") (name "unconnected-(IC3-AREF-Pad20)") (class "Default")
      (node (ref "IC3") (pin "20") (pinfunction "AREF_20") (pintype "passive"))
    )
    (net (code "68") (name "unconnected-(IC3-PB0(ICP)-Pad12)") (class "Default")
      (node (ref "IC3") (pin "12") (pinfunction "PB0(ICP)_12") (pintype "bidirectional"))
    )
    (net (code "69") (name "unconnected-(IC3-PB1(OC1A)-Pad13)") (class "Default")
      (node (ref "IC3") (pin "13") (pinfunction "PB1(OC1A)_13") (pintype "bidirectional"))
    )
    (net (code "70") (name "unconnected-(IC3-PB2(SS{slash}OC1B)-Pad14)") (class "Default")
      (node (ref "IC3") (pin "14") (pinfunction "PB2(SS/OC1B)_14") (pintype "bidirectional"))
    )
    (net (code "71") (name "unconnected-(IC3-PC2(ADC2)-Pad25)") (class "Default")
      (node (ref "IC3") (pin "25") (pinfunction "PC2(ADC2)_25") (pintype "bidirectional"))
    )
    (net (code "72") (name "unconnected-(IC3-PC3(ADC3)-Pad26)") (class "Default")
      (node (ref "IC3") (pin "26") (pinfunction "PC3(ADC3)_26") (pintype "bidirectional"))
    )
    (net (code "73") (name "unconnected-(IC3-PD2(INT0)-Pad32)") (class "Default")
      (node (ref "IC3") (pin "32") (pinfunction "PD2(INT0)_32") (pintype "bidirectional"))
    )
    (net (code "74") (name "unconnected-(IC3-PD3(INT1)-Pad1)") (class "Default")
      (node (ref "IC3") (pin "1") (pinfunction "PD3(INT1)_1") (pintype "bidirectional"))
    )
    (net (code "75") (name "unconnected-(IC3-PD4(XCK{slash}T0)-Pad2)") (class "Default")
      (node (ref "IC3") (pin "2") (pinfunction "PD4(XCK/T0)_2") (pintype "bidirectional"))
    )
    (net (code "76") (name "unconnected-(IC3-PD5(T1)-Pad9)") (class "Default")
      (node (ref "IC3") (pin "9") (pinfunction "PD5(T1)_9") (pintype "bidirectional"))
    )
    (net (code "77") (name "unconnected-(IC3-PD6(AIN0)-Pad10)") (class "Default")
      (node (ref "IC3") (pin "10") (pinfunction "PD6(AIN0)_10") (pintype "bidirectional"))
    )
    (net (code "78") (name "unconnected-(IC3-PD7(AIN1)-Pad11)") (class "Default")
      (node (ref "IC3") (pin "11") (pinfunction "PD7(AIN1)_11") (pintype "bidirectional"))
    )
    (net (code "79") (name "unconnected-(J1AA-MS-PadC28)") (class "Default")
      (node (ref "J1") (pin "C28") (pinfunction "MS_C28") (pintype "passive"))
    )
    (net (code "80") (name "unconnected-(J1AD-MS-PadC4)") (class "Default")
      (node (ref "J1") (pin "C4") (pinfunction "MS_C4") (pintype "passive"))
    )
    (net (code "81") (name "unconnected-(J1AE-MS-PadC6)") (class "Default")
      (node (ref "J1") (pin "C6") (pinfunction "MS_C6") (pintype "passive"))
    )
    (net (code "82") (name "unconnected-(J1E-MS-PadA18)") (class "Default")
      (node (ref "J1") (pin "A18") (pinfunction "MS_A18") (pintype "passive"))
    )
    (net (code "83") (name "unconnected-(J1I-MS-PadA24)") (class "Default")
      (node (ref "J1") (pin "A24") (pinfunction "MS_A24") (pintype "passive"))
    )
    (net (code "84") (name "unconnected-(J1J-MS-PadA26)") (class "Default")
      (node (ref "J1") (pin "A26") (pinfunction "MS_A26") (pintype "passive"))
    )
    (net (code "85") (name "unconnected-(J1K-MS-PadA28)") (class "Default")
      (node (ref "J1") (pin "A28") (pinfunction "MS_A28") (pintype "passive"))
    )
    (net (code "86") (name "unconnected-(J1N-MS-PadA4)") (class "Default")
      (node (ref "J1") (pin "A4") (pinfunction "MS_A4") (pintype "passive"))
    )
    (net (code "87") (name "unconnected-(J1U-MS-PadC18)") (class "Default")
      (node (ref "J1") (pin "C18") (pinfunction "MS_C18") (pintype "passive"))
    )
    (net (code "88") (name "unconnected-(J1Y-MS-PadC24)") (class "Default")
      (node (ref "J1") (pin "C24") (pinfunction "MS_C24") (pintype "passive"))
    )
    (net (code "89") (name "unconnected-(J1Z-MS-PadC26)") (class "Default")
      (node (ref "J1") (pin "C26") (pinfunction "MS_C26") (pintype "passive"))
    )
  )
)
